# Spare_Pins.net
KiCad netlist of a schematic drawn in Altium Designer
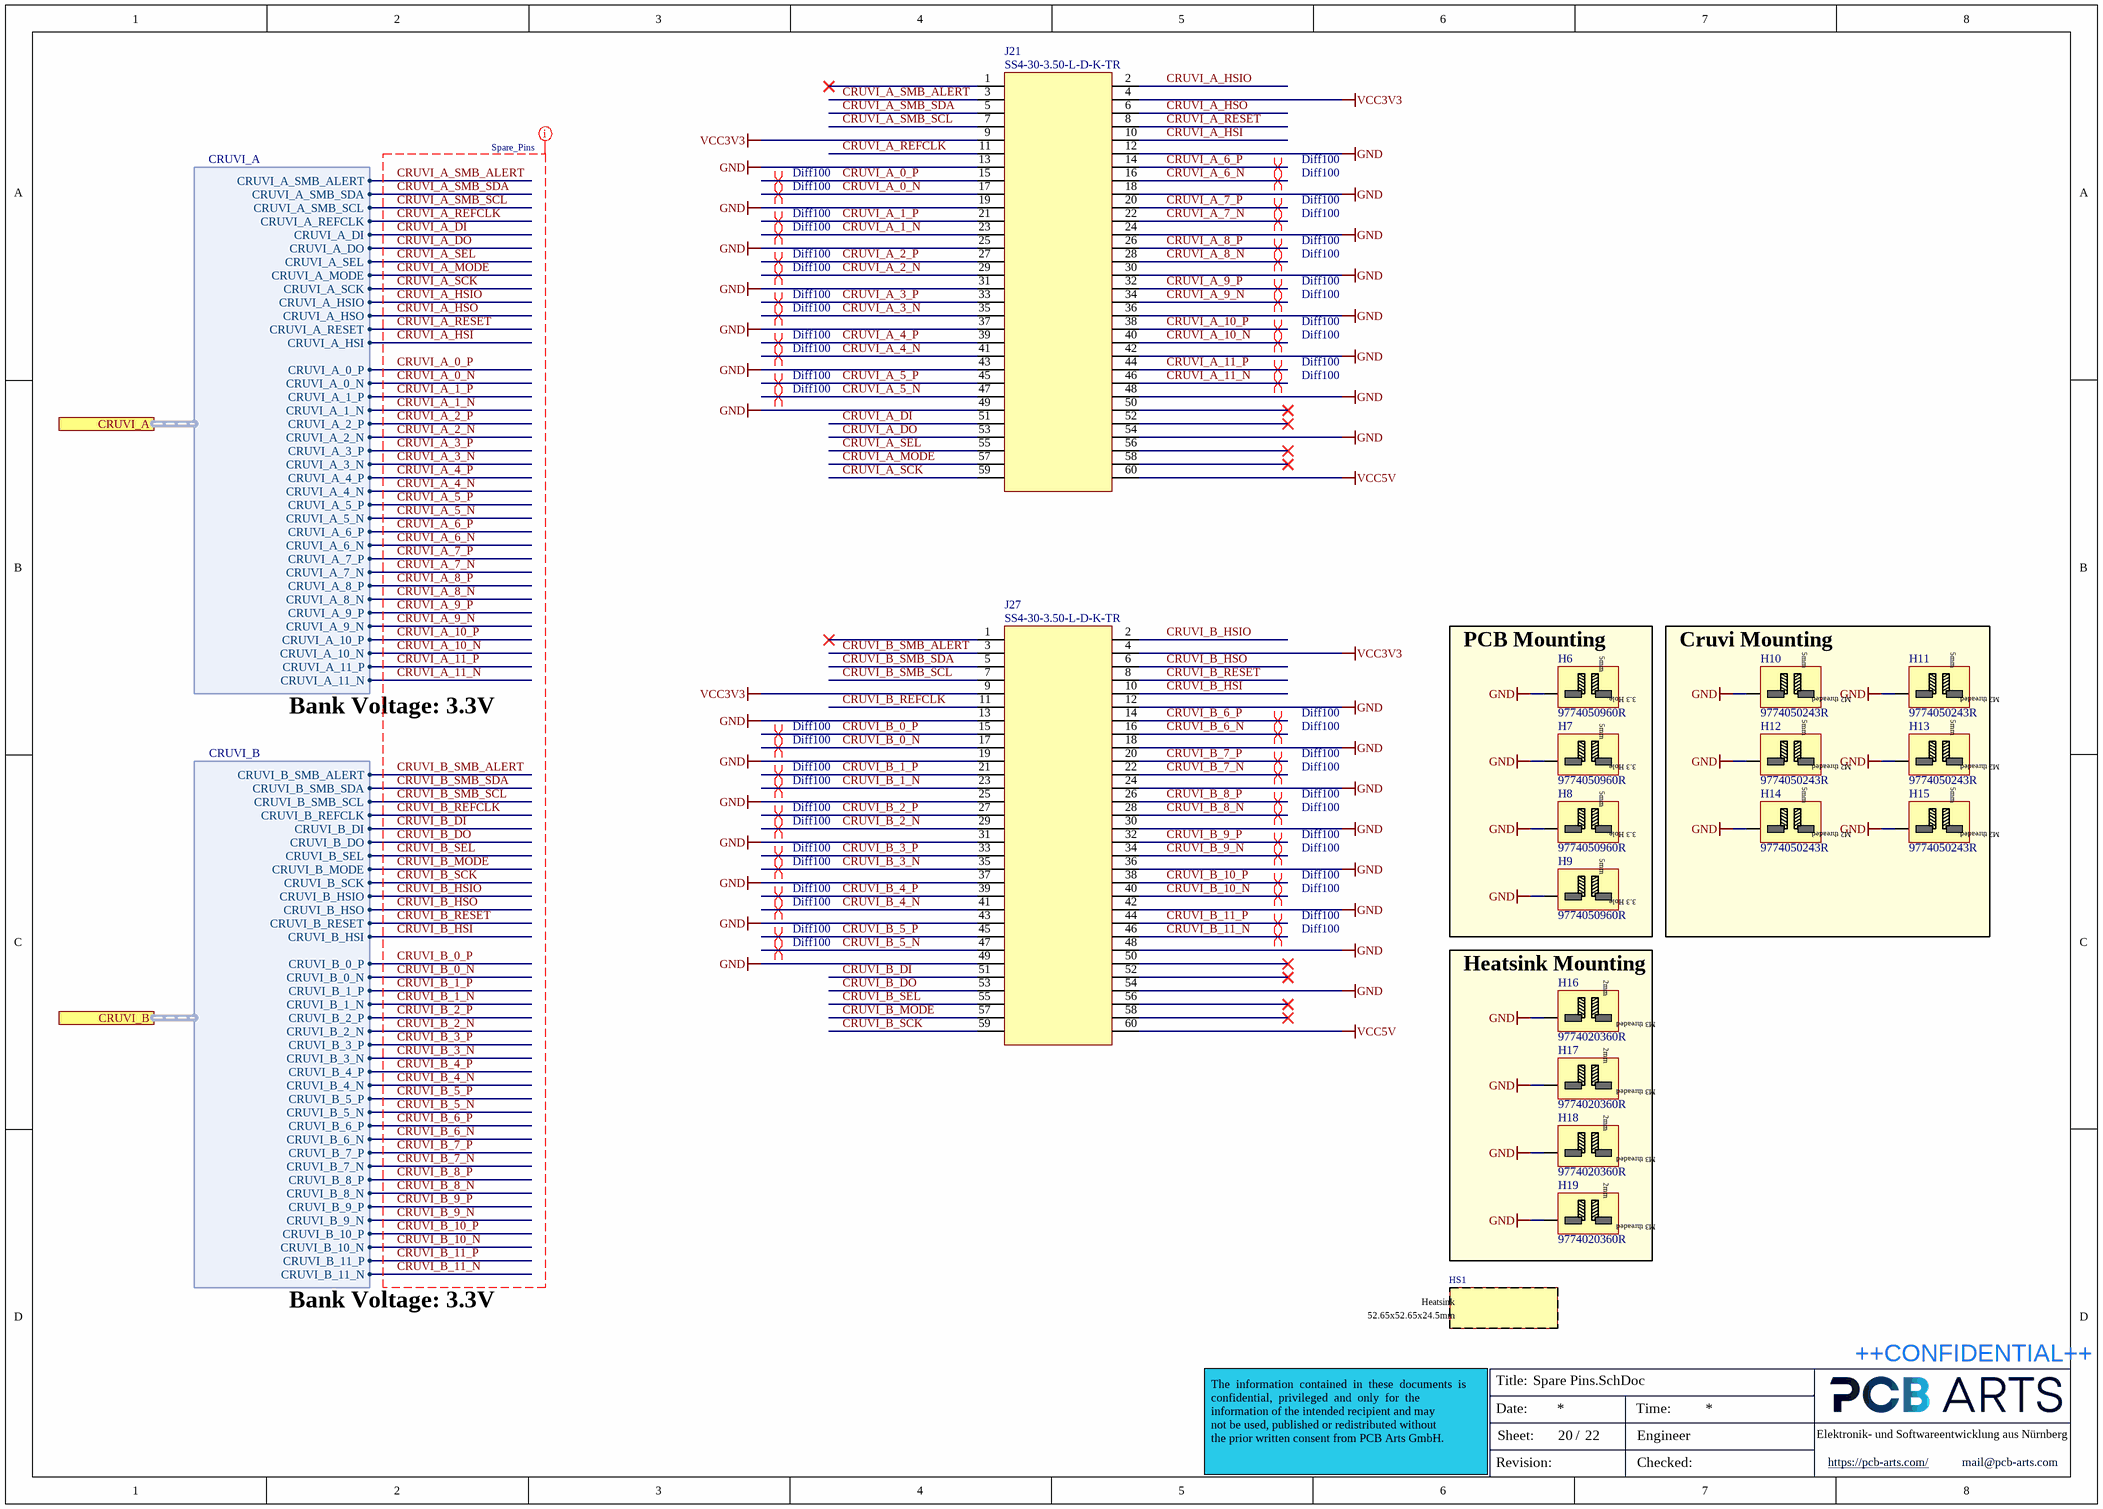
[diagram p0: Spare Pins.SchDoc]

(export (version "E")
  (design (tool "Eeschema 10.0.6"))
  (components
    (comp (ref "H6")
      (value "9774050960R")
      (footprint "Electro_Mech:9774050960R")
      (description "Würth Standoff TH3.3 h:5mm 9774050960R")
      (libsource (lib "Electro_Mech") (part "Würth Standoff TH3.3 h{colon}5mm"))
    )
    (comp (ref "H7")
      (value "9774050960R")
      (footprint "Electro_Mech:9774050960R")
      (description "Würth Standoff TH3.3 h:5mm 9774050960R")
      (libsource (lib "Electro_Mech") (part "Würth Standoff TH3.3 h{colon}5mm"))
    )
    (comp (ref "H8")
      (value "9774050960R")
      (footprint "Electro_Mech:9774050960R")
      (description "Würth Standoff TH3.3 h:5mm 9774050960R")
      (libsource (lib "Electro_Mech") (part "Würth Standoff TH3.3 h{colon}5mm"))
    )
    (comp (ref "H9")
      (value "9774050960R")
      (footprint "Electro_Mech:9774050960R")
      (description "Würth Standoff TH3.3 h:5mm 9774050960R")
      (libsource (lib "Electro_Mech") (part "Würth Standoff TH3.3 h{colon}5mm"))
    )
    (comp (ref "H10")
      (value "9774050243R")
      (footprint "Electro_Mech:9774050243R")
      (description "Würth Standoff M2 h:5mm 9774050243R")
      (libsource (lib "Electro_Mech") (part "Würth Standoff M2 h{colon}5mm"))
    )
    (comp (ref "H11")
      (value "9774050243R")
      (footprint "Electro_Mech:9774050243R")
      (description "Würth Standoff M2 h:5mm 9774050243R")
      (libsource (lib "Electro_Mech") (part "Würth Standoff M2 h{colon}5mm"))
    )
    (comp (ref "H12")
      (value "9774050243R")
      (footprint "Electro_Mech:9774050243R")
      (description "Würth Standoff M2 h:5mm 9774050243R")
      (libsource (lib "Electro_Mech") (part "Würth Standoff M2 h{colon}5mm"))
    )
    (comp (ref "H13")
      (value "9774050243R")
      (footprint "Electro_Mech:9774050243R")
      (description "Würth Standoff M2 h:5mm 9774050243R")
      (libsource (lib "Electro_Mech") (part "Würth Standoff M2 h{colon}5mm"))
    )
    (comp (ref "H14")
      (value "9774050243R")
      (footprint "Electro_Mech:9774050243R")
      (description "Würth Standoff M2 h:5mm 9774050243R")
      (libsource (lib "Electro_Mech") (part "Würth Standoff M2 h{colon}5mm"))
    )
    (comp (ref "H15")
      (value "9774050243R")
      (footprint "Electro_Mech:9774050243R")
      (description "Würth Standoff M2 h:5mm 9774050243R")
      (libsource (lib "Electro_Mech") (part "Würth Standoff M2 h{colon}5mm"))
    )
    (comp (ref "H16")
      (value "9774020360R")
      (footprint "Electro_Mech:9774020360R")
      (description "Würth Standoff M3 h:2mm 9774020360R")
      (libsource (lib "Electro_Mech") (part "Würth Standoff M3 h{colon}2mm"))
    )
    (comp (ref "H17")
      (value "9774020360R")
      (footprint "Electro_Mech:9774020360R")
      (description "Würth Standoff M3 h:2mm 9774020360R")
      (libsource (lib "Electro_Mech") (part "Würth Standoff M3 h{colon}2mm"))
    )
    (comp (ref "H18")
      (value "9774020360R")
      (footprint "Electro_Mech:9774020360R")
      (description "Würth Standoff M3 h:2mm 9774020360R")
      (libsource (lib "Electro_Mech") (part "Würth Standoff M3 h{colon}2mm"))
    )
    (comp (ref "H19")
      (value "9774020360R")
      (footprint "Electro_Mech:9774020360R")
      (description "Würth Standoff M3 h:2mm 9774020360R")
      (libsource (lib "Electro_Mech") (part "Würth Standoff M3 h{colon}2mm"))
    )
    (comp (ref "HS1")
      (value "Heatsink Assembly 52.65x52.65x24.5mm")
      (footprint "Electro_Mech:ATS-61500W-C2-R0")
      (description "Machined Copper Heatsink for GaN Devices")
      (libsource (lib "Electro_Mech") (part "ATS-61500W-C2-R0_Heatsink Assembly 52.65x52.65x24.5mm"))
    )
    (comp (ref "J21")
      (value "SS4-30-3.50-L-D-K-TR")
      (footprint "SS4-30-3.50-L-D-K-TR")
      (description "Platine-zu-Platine & Mezzanine-Steckverbinder 0.40 mm Micro Blade & Beam Ultra Fine Pitch Socket")
      (libsource (lib "Conn") (part "SS4-30-3.50-L-D-K-TR"))
    )
    (comp (ref "J27")
      (value "SS4-30-3.50-L-D-K-TR")
      (footprint "SS4-30-3.50-L-D-K-TR")
      (description "Platine-zu-Platine & Mezzanine-Steckverbinder 0.40 mm Micro Blade & Beam Ultra Fine Pitch Socket")
      (libsource (lib "Conn") (part "SS4-30-3.50-L-D-K-TR"))
    )
  )
  (nets
    (net (code "3") (name "/CRUVI_A_0_N") (class "Default") (node (ref "J21") (pin "17") (pintype "passive")))
    (net (code "4") (name "/CRUVI_A_0_P") (class "Default") (node (ref "J21") (pin "15") (pintype "passive")))
    (net (code "5") (name "/CRUVI_A_1_N") (class "Default") (node (ref "J21") (pin "23") (pintype "passive")))
    (net (code "6") (name "/CRUVI_A_1_P") (class "Default") (node (ref "J21") (pin "21") (pintype "passive")))
    (net (code "7") (name "/CRUVI_A_2_N") (class "Default") (node (ref "J21") (pin "29") (pintype "passive")))
    (net (code "8") (name "/CRUVI_A_2_P") (class "Default") (node (ref "J21") (pin "27") (pintype "passive")))
    (net (code "9") (name "/CRUVI_A_3_N") (class "Default") (node (ref "J21") (pin "35") (pintype "passive")))
    (net (code "10") (name "/CRUVI_A_3_P") (class "Default")
      (node (ref "J21") (pin "33") (pintype "passive"))
    )
    (net (code "11") (name "/CRUVI_A_4_N") (class "Default")
      (node (ref "J21") (pin "41") (pintype "passive"))
    )
    (net (code "12") (name "/CRUVI_A_4_P") (class "Default")
      (node (ref "J21") (pin "39") (pintype "passive"))
    )
    (net (code "13") (name "/CRUVI_A_5_N") (class "Default")
      (node (ref "J21") (pin "47") (pintype "passive"))
    )
    (net (code "14") (name "/CRUVI_A_5_P") (class "Default")
      (node (ref "J21") (pin "45") (pintype "passive"))
    )
    (net (code "15") (name "/CRUVI_A_6_N") (class "Default")
      (node (ref "J21") (pin "16") (pintype "passive"))
    )
    (net (code "16") (name "/CRUVI_A_6_P") (class "Default")
      (node (ref "J21") (pin "14") (pintype "passive"))
    )
    (net (code "17") (name "/CRUVI_A_7_N") (class "Default")
      (node (ref "J21") (pin "22") (pintype "passive"))
    )
    (net (code "18") (name "/CRUVI_A_7_P") (class "Default")
      (node (ref "J21") (pin "20") (pintype "passive"))
    )
    (net (code "19") (name "/CRUVI_A_8_N") (class "Default")
      (node (ref "J21") (pin "28") (pintype "passive"))
    )
    (net (code "20") (name "/CRUVI_A_8_P") (class "Default")
      (node (ref "J21") (pin "26") (pintype "passive"))
    )
    (net (code "21") (name "/CRUVI_A_9_N") (class "Default")
      (node (ref "J21") (pin "34") (pintype "passive"))
    )
    (net (code "22") (name "/CRUVI_A_9_P") (class "Default")
      (node (ref "J21") (pin "32") (pintype "passive"))
    )
    (net (code "23") (name "/CRUVI_A_10_N") (class "Default")
      (node (ref "J21") (pin "40") (pintype "passive"))
    )
    (net (code "24") (name "/CRUVI_A_10_P") (class "Default")
      (node (ref "J21") (pin "38") (pintype "passive"))
    )
    (net (code "25") (name "/CRUVI_A_11_N") (class "Default")
      (node (ref "J21") (pin "46") (pintype "passive"))
    )
    (net (code "26") (name "/CRUVI_A_11_P") (class "Default")
      (node (ref "J21") (pin "44") (pintype "passive"))
    )
    (net (code "27") (name "/CRUVI_A_DI") (class "Default") (node (ref "J21") (pin "51") (pintype "passive")))
    (net (code "28") (name "/CRUVI_A_DO") (class "Default") (node (ref "J21") (pin "53") (pintype "passive")))
    (net (code "29") (name "/CRUVI_A_HSI") (class "Default")
      (node (ref "J21") (pin "10") (pintype "passive"))
    )
    (net (code "30") (name "/CRUVI_A_HSIO") (class "Default")
      (node (ref "J21") (pin "2") (pintype "passive"))
    )
    (net (code "31") (name "/CRUVI_A_HSO") (class "Default") (node (ref "J21") (pin "6") (pintype "passive")))
    (net (code "32") (name "/CRUVI_A_MODE") (class "Default")
      (node (ref "J21") (pin "57") (pintype "passive"))
    )
    (net (code "33") (name "/CRUVI_A_REFCLK") (class "Default")
      (node (ref "J21") (pin "11") (pintype "passive"))
    )
    (net (code "34") (name "/CRUVI_A_RESET") (class "Default")
      (node (ref "J21") (pin "8") (pintype "passive"))
    )
    (net (code "35") (name "/CRUVI_A_SCK") (class "Default")
      (node (ref "J21") (pin "59") (pintype "passive"))
    )
    (net (code "36") (name "/CRUVI_A_SEL") (class "Default")
      (node (ref "J21") (pin "55") (pintype "passive"))
    )
    (net (code "37") (name "/CRUVI_A_SMB_ALERT") (class "Default")
      (node (ref "J21") (pin "3") (pintype "passive"))
    )
    (net (code "38") (name "/CRUVI_A_SMB_SCL") (class "Default")
      (node (ref "J21") (pin "7") (pintype "passive"))
    )
    (net (code "39") (name "/CRUVI_A_SMB_SDA") (class "Default")
      (node (ref "J21") (pin "5") (pintype "passive"))
    )
    (net (code "40") (name "/CRUVI_B_0_N") (class "Default")
      (node (ref "J27") (pin "17") (pintype "passive"))
    )
    (net (code "41") (name "/CRUVI_B_0_P") (class "Default")
      (node (ref "J27") (pin "15") (pintype "passive"))
    )
    (net (code "42") (name "/CRUVI_B_1_N") (class "Default")
      (node (ref "J27") (pin "23") (pintype "passive"))
    )
    (net (code "43") (name "/CRUVI_B_1_P") (class "Default")
      (node (ref "J27") (pin "21") (pintype "passive"))
    )
    (net (code "44") (name "/CRUVI_B_2_N") (class "Default")
      (node (ref "J27") (pin "29") (pintype "passive"))
    )
    (net (code "45") (name "/CRUVI_B_2_P") (class "Default")
      (node (ref "J27") (pin "27") (pintype "passive"))
    )
    (net (code "46") (name "/CRUVI_B_3_N") (class "Default")
      (node (ref "J27") (pin "35") (pintype "passive"))
    )
    (net (code "47") (name "/CRUVI_B_3_P") (class "Default")
      (node (ref "J27") (pin "33") (pintype "passive"))
    )
    (net (code "48") (name "/CRUVI_B_4_N") (class "Default")
      (node (ref "J27") (pin "41") (pintype "passive"))
    )
    (net (code "49") (name "/CRUVI_B_4_P") (class "Default")
      (node (ref "J27") (pin "39") (pintype "passive"))
    )
    (net (code "50") (name "/CRUVI_B_5_N") (class "Default")
      (node (ref "J27") (pin "47") (pintype "passive"))
    )
    (net (code "51") (name "/CRUVI_B_5_P") (class "Default")
      (node (ref "J27") (pin "45") (pintype "passive"))
    )
    (net (code "52") (name "/CRUVI_B_6_N") (class "Default")
      (node (ref "J27") (pin "16") (pintype "passive"))
    )
    (net (code "53") (name "/CRUVI_B_6_P") (class "Default")
      (node (ref "J27") (pin "14") (pintype "passive"))
    )
    (net (code "54") (name "/CRUVI_B_7_N") (class "Default")
      (node (ref "J27") (pin "22") (pintype "passive"))
    )
    (net (code "55") (name "/CRUVI_B_7_P") (class "Default")
      (node (ref "J27") (pin "20") (pintype "passive"))
    )
    (net (code "56") (name "/CRUVI_B_8_N") (class "Default")
      (node (ref "J27") (pin "28") (pintype "passive"))
    )
    (net (code "57") (name "/CRUVI_B_8_P") (class "Default")
      (node (ref "J27") (pin "26") (pintype "passive"))
    )
    (net (code "58") (name "/CRUVI_B_9_N") (class "Default")
      (node (ref "J27") (pin "34") (pintype "passive"))
    )
    (net (code "59") (name "/CRUVI_B_9_P") (class "Default")
      (node (ref "J27") (pin "32") (pintype "passive"))
    )
    (net (code "60") (name "/CRUVI_B_10_N") (class "Default")
      (node (ref "J27") (pin "40") (pintype "passive"))
    )
    (net (code "61") (name "/CRUVI_B_10_P") (class "Default")
      (node (ref "J27") (pin "38") (pintype "passive"))
    )
    (net (code "62") (name "/CRUVI_B_11_N") (class "Default")
      (node (ref "J27") (pin "46") (pintype "passive"))
    )
    (net (code "63") (name "/CRUVI_B_11_P") (class "Default")
      (node (ref "J27") (pin "44") (pintype "passive"))
    )
    (net (code "64") (name "/CRUVI_B_DI") (class "Default") (node (ref "J27") (pin "51") (pintype "passive")))
    (net (code "65") (name "/CRUVI_B_DO") (class "Default") (node (ref "J27") (pin "53") (pintype "passive")))
    (net (code "66") (name "/CRUVI_B_HSI") (class "Default")
      (node (ref "J27") (pin "10") (pintype "passive"))
    )
    (net (code "67") (name "/CRUVI_B_HSIO") (class "Default")
      (node (ref "J27") (pin "2") (pintype "passive"))
    )
    (net (code "68") (name "/CRUVI_B_HSO") (class "Default") (node (ref "J27") (pin "6") (pintype "passive")))
    (net (code "69") (name "/CRUVI_B_MODE") (class "Default")
      (node (ref "J27") (pin "57") (pintype "passive"))
    )
    (net (code "70") (name "/CRUVI_B_REFCLK") (class "Default")
      (node (ref "J27") (pin "11") (pintype "passive"))
    )
    (net (code "71") (name "/CRUVI_B_RESET") (class "Default")
      (node (ref "J27") (pin "8") (pintype "passive"))
    )
    (net (code "72") (name "/CRUVI_B_SCK") (class "Default")
      (node (ref "J27") (pin "59") (pintype "passive"))
    )
    (net (code "73") (name "/CRUVI_B_SEL") (class "Default")
      (node (ref "J27") (pin "55") (pintype "passive"))
    )
    (net (code "74") (name "/CRUVI_B_SMB_ALERT") (class "Default")
      (node (ref "J27") (pin "3") (pintype "passive"))
    )
    (net (code "75") (name "/CRUVI_B_SMB_SCL") (class "Default")
      (node (ref "J27") (pin "7") (pintype "passive"))
    )
    (net (code "76") (name "/CRUVI_B_SMB_SDA") (class "Default")
      (node (ref "J27") (pin "5") (pintype "passive"))
    )
    (net (code "79") (name "GND") (class "Default")
      (node (ref "H10") (pin "1") (pinfunction "1_1") (pintype "passive"))
      (node (ref "H11") (pin "1") (pinfunction "1_1") (pintype "passive"))
      (node (ref "H12") (pin "1") (pinfunction "1_1") (pintype "passive"))
      (node (ref "H13") (pin "1") (pinfunction "1_1") (pintype "passive"))
      (node (ref "H14") (pin "1") (pinfunction "1_1") (pintype "passive"))
      (node (ref "H15") (pin "1") (pinfunction "1_1") (pintype "passive"))
      (node (ref "H16") (pin "1") (pinfunction "1_1") (pintype "passive"))
      (node (ref "H17") (pin "1") (pinfunction "1_1") (pintype "passive"))
      (node (ref "H18") (pin "1") (pinfunction "1_1") (pintype "passive"))
      (node (ref "H19") (pin "1") (pinfunction "1_1") (pintype "passive"))
      (node (ref "H6") (pin "1") (pinfunction "1_1") (pintype "passive"))
      (node (ref "H7") (pin "1") (pinfunction "1_1") (pintype "passive"))
      (node (ref "H8") (pin "1") (pinfunction "1_1") (pintype "passive"))
      (node (ref "H9") (pin "1") (pinfunction "1_1") (pintype "passive"))
      (node (ref "J21") (pin "12") (pintype "passive"))
      (node (ref "J21") (pin "13") (pintype "passive"))
      (node (ref "J21") (pin "18") (pintype "passive"))
      (node (ref "J21") (pin "19") (pintype "passive"))
      (node (ref "J21") (pin "24") (pintype "passive"))
      (node (ref "J21") (pin "25") (pintype "passive"))
      (node (ref "J21") (pin "30") (pintype "passive"))
      (node (ref "J21") (pin "31") (pintype "passive"))
      (node (ref "J21") (pin "36") (pintype "passive"))
      (node (ref "J21") (pin "37") (pintype "passive"))
      (node (ref "J21") (pin "42") (pintype "passive"))
      (node (ref "J21") (pin "43") (pintype "passive"))
      (node (ref "J21") (pin "48") (pintype "passive"))
      (node (ref "J21") (pin "49") (pintype "passive"))
      (node (ref "J21") (pin "54") (pintype "passive"))
      (node (ref "J27") (pin "12") (pintype "passive"))
      (node (ref "J27") (pin "13") (pintype "passive"))
      (node (ref "J27") (pin "18") (pintype "passive"))
      (node (ref "J27") (pin "19") (pintype "passive"))
      (node (ref "J27") (pin "24") (pintype "passive"))
      (node (ref "J27") (pin "25") (pintype "passive"))
      (node (ref "J27") (pin "30") (pintype "passive"))
      (node (ref "J27") (pin "31") (pintype "passive"))
      (node (ref "J27") (pin "36") (pintype "passive"))
      (node (ref "J27") (pin "37") (pintype "passive"))
      (node (ref "J27") (pin "42") (pintype "passive"))
      (node (ref "J27") (pin "43") (pintype "passive"))
      (node (ref "J27") (pin "48") (pintype "passive"))
      (node (ref "J27") (pin "49") (pintype "passive"))
      (node (ref "J27") (pin "54") (pintype "passive"))
    )
    (net (code "80") (name "VCC3V3") (class "Default")
      (node (ref "J21") (pin "4") (pintype "passive"))
      (node (ref "J21") (pin "9") (pintype "passive"))
      (node (ref "J27") (pin "4") (pintype "passive"))
      (node (ref "J27") (pin "9") (pintype "passive"))
    )
    (net (code "81") (name "VCC5V") (class "Default")
      (node (ref "J21") (pin "60") (pintype "passive"))
      (node (ref "J27") (pin "60") (pintype "passive"))
    )
    (net (code "82") (name "unconnected-(J21-Pad1)") (class "Default")
      (node (ref "J21") (pin "1") (pintype "passive+no_connect"))
    )
    (net (code "83") (name "unconnected-(J21-Pad50)") (class "Default")
      (node (ref "J21") (pin "50") (pintype "passive+no_connect"))
    )
    (net (code "84") (name "unconnected-(J21-Pad52)") (class "Default")
      (node (ref "J21") (pin "52") (pintype "passive+no_connect"))
    )
    (net (code "85") (name "unconnected-(J21-Pad56)") (class "Default")
      (node (ref "J21") (pin "56") (pintype "passive+no_connect"))
    )
    (net (code "86") (name "unconnected-(J21-Pad58)") (class "Default")
      (node (ref "J21") (pin "58") (pintype "passive+no_connect"))
    )
    (net (code "87") (name "unconnected-(J27-Pad1)") (class "Default")
      (node (ref "J27") (pin "1") (pintype "passive+no_connect"))
    )
    (net (code "88") (name "unconnected-(J27-Pad50)") (class "Default")
      (node (ref "J27") (pin "50") (pintype "passive+no_connect"))
    )
    (net (code "89") (name "unconnected-(J27-Pad52)") (class "Default")
      (node (ref "J27") (pin "52") (pintype "passive+no_connect"))
    )
    (net (code "90") (name "unconnected-(J27-Pad56)") (class "Default")
      (node (ref "J27") (pin "56") (pintype "passive+no_connect"))
    )
    (net (code "91") (name "unconnected-(J27-Pad58)") (class "Default")
      (node (ref "J27") (pin "58") (pintype "passive+no_connect"))
    )
  )
)
